# ESP32_sparrow_old_good.net
KiCad netlist of a schematic drawn in EAGLE
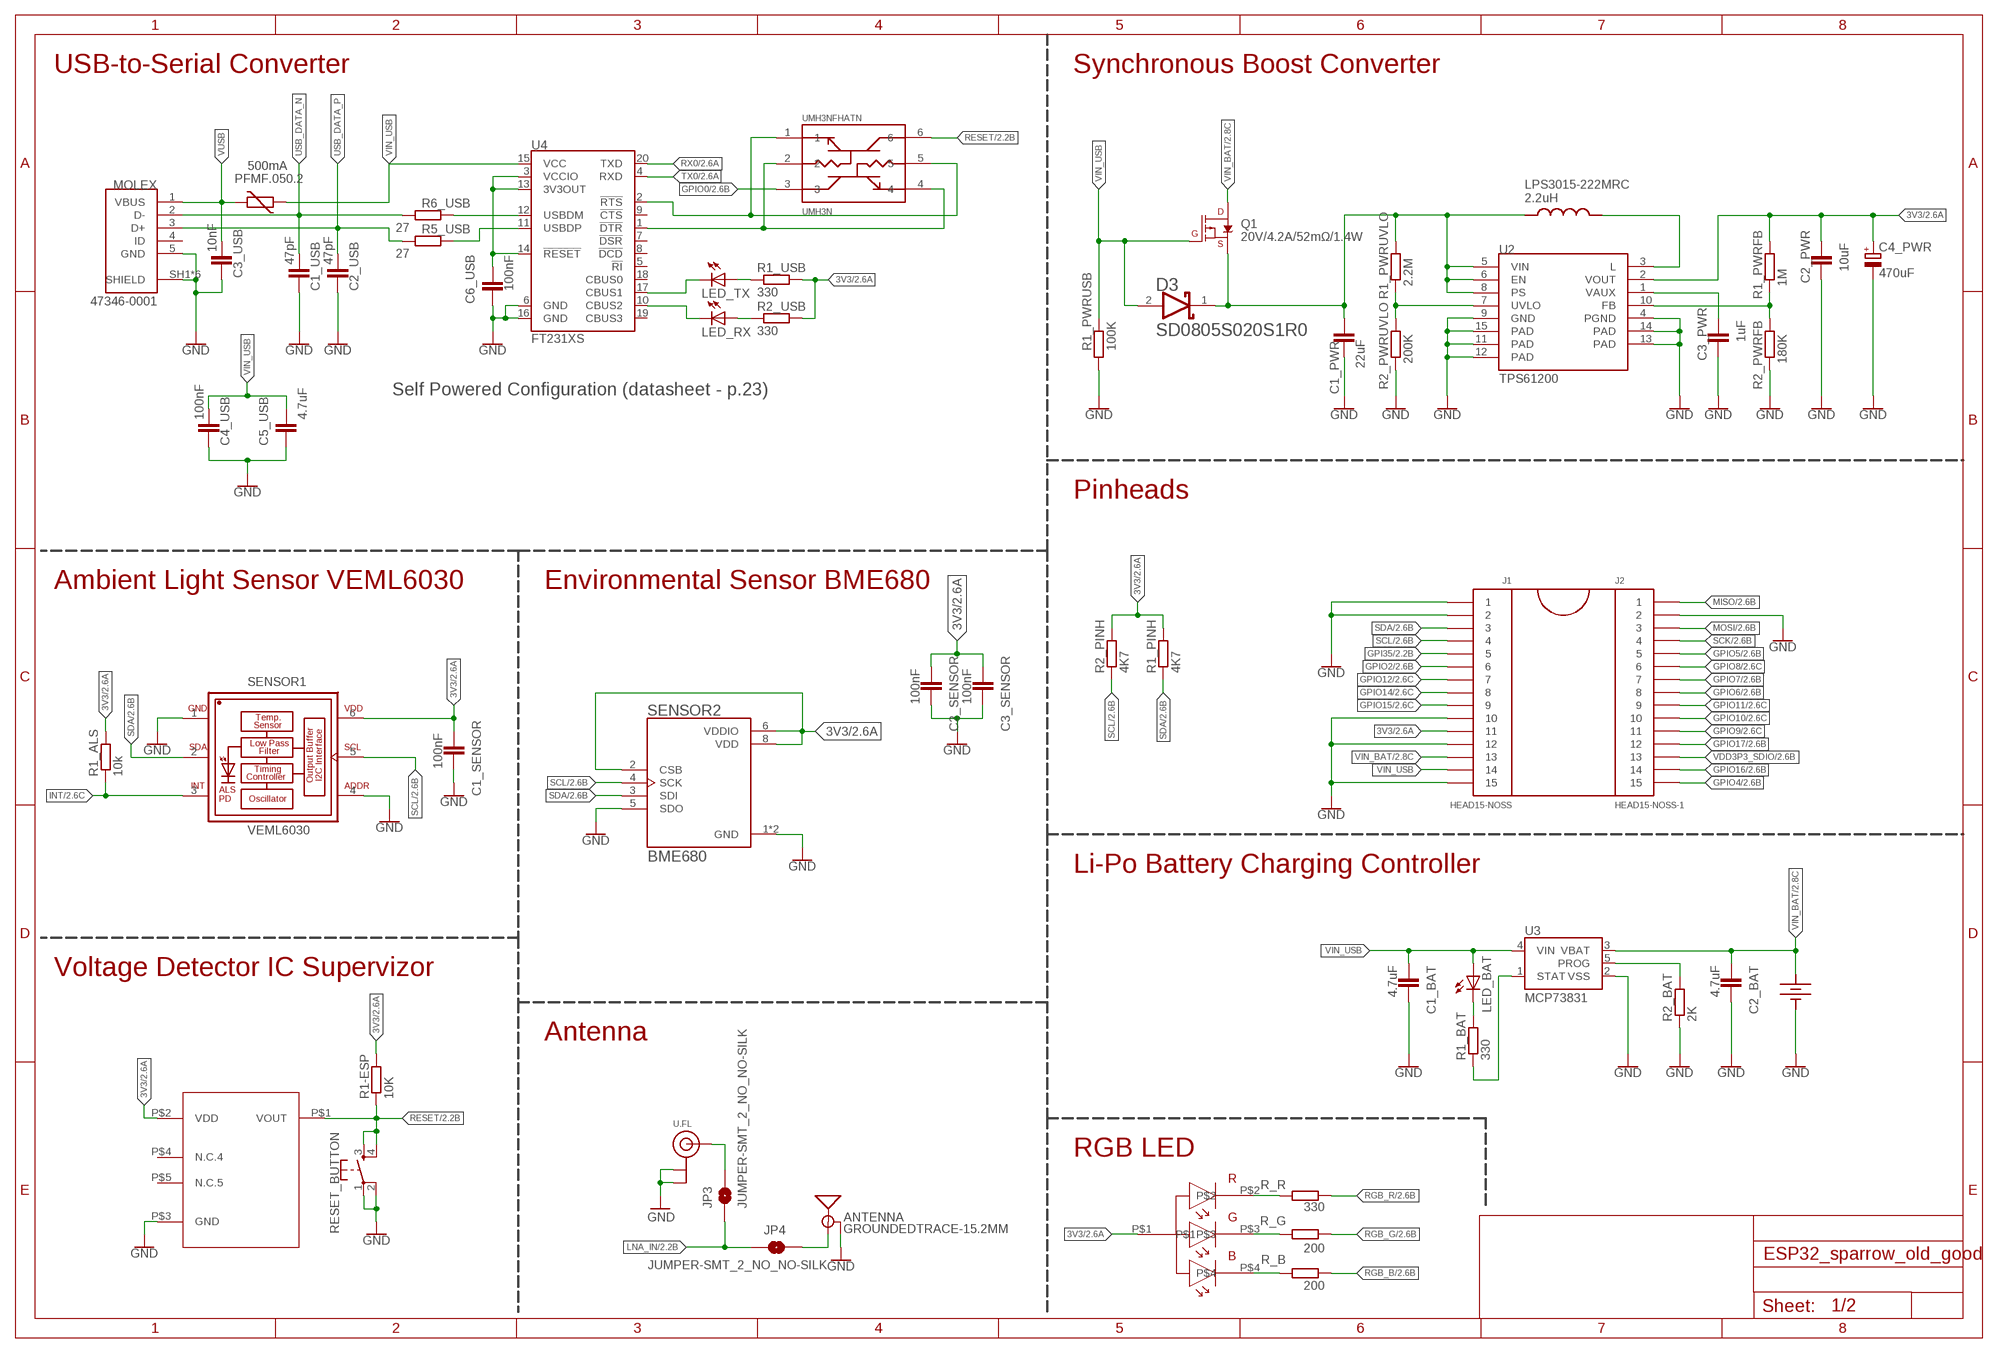
[diagram p0: schematic, sheet 1]
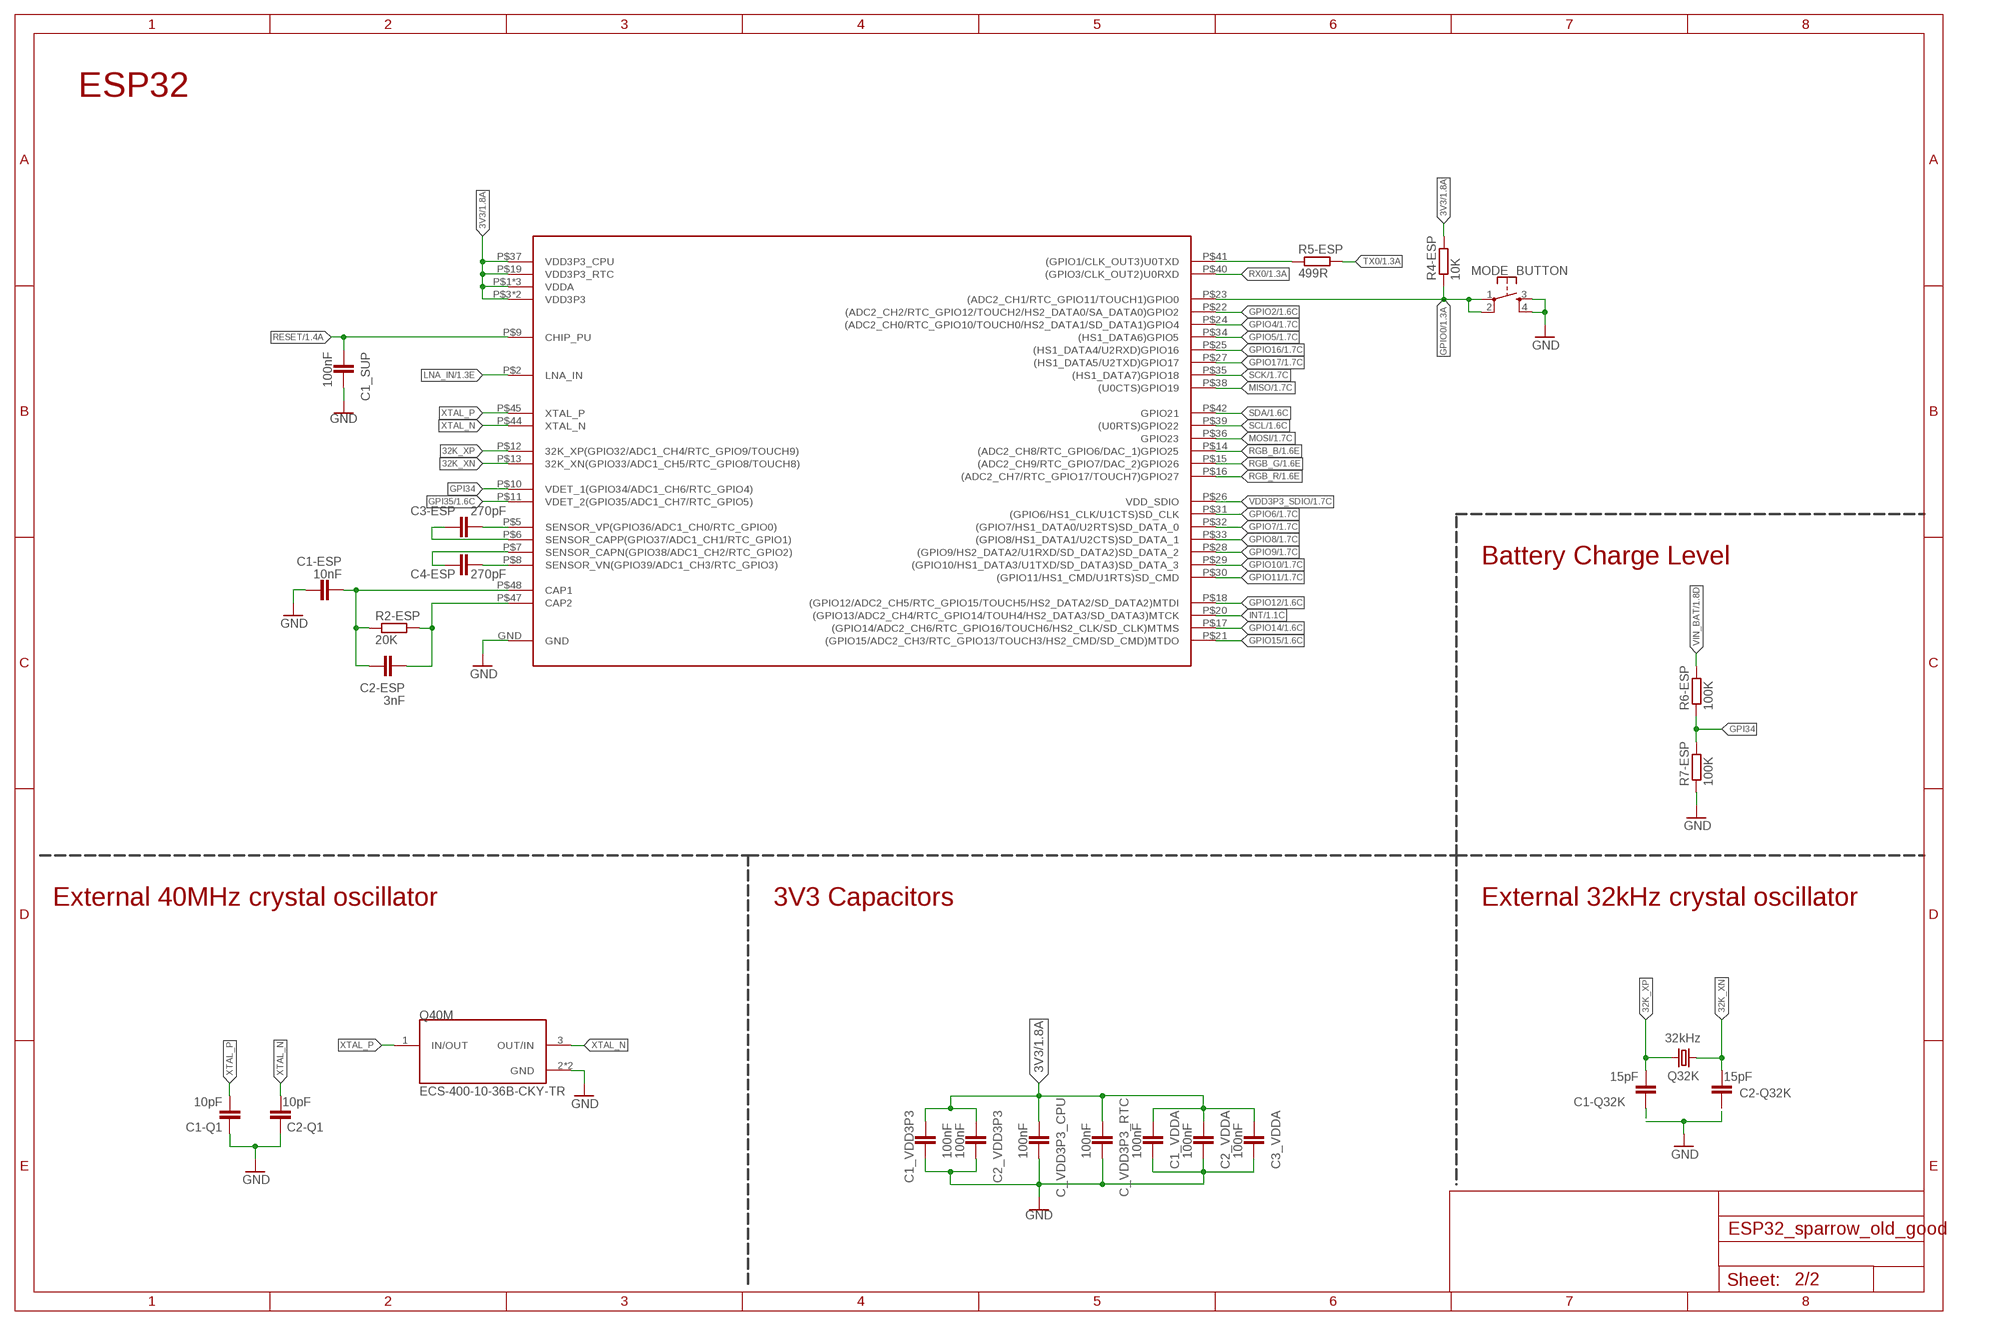
[diagram p1: schematic, sheet 2]

(export (version "E")
  (design (tool "Eeschema 10.0.6"))
  (components
    (comp (ref "C1-ESP")
      (value "10nF")
      (footprint "eagle-import:C0402")
      (libsource (lib "eagle-import") (part "CC0402"))
    )
    (comp (ref "C1-Q1")
      (value "10pF")
      (footprint "eagle-import:C0402")
      (libsource (lib "eagle-import") (part "CC0402"))
    )
    (comp (ref "C1-Q32K")
      (value "15pF")
      (footprint "eagle-import:C0402")
      (libsource (lib "eagle-import") (part "CC0402"))
    )
    (comp (ref "C1_SUP")
      (value "100nF")
      (footprint "eagle-import:C0402")
      (libsource (lib "eagle-import") (part "CC0402"))
    )
    (comp (ref "C1_VDD3P3")
      (value "100nF")
      (footprint "eagle-import:C0402")
      (libsource (lib "eagle-import") (part "CC0402"))
    )
    (comp (ref "C1_VDDA")
      (value "100nF")
      (footprint "eagle-import:C0402")
      (libsource (lib "eagle-import") (part "CC0402"))
    )
    (comp (ref "C2-ESP")
      (value "3nF")
      (footprint "eagle-import:C0402")
      (libsource (lib "eagle-import") (part "CC0402"))
    )
    (comp (ref "C2-Q1")
      (value "10pF")
      (footprint "eagle-import:C0402")
      (libsource (lib "eagle-import") (part "CC0402"))
    )
    (comp (ref "C2-Q32K")
      (value "15pF")
      (footprint "eagle-import:C0402")
      (libsource (lib "eagle-import") (part "CC0402"))
    )
    (comp (ref "C2_VDD3P3")
      (value "100nF")
      (footprint "eagle-import:C0402")
      (libsource (lib "eagle-import") (part "CC0402"))
    )
    (comp (ref "C2_VDDA")
      (value "100nF")
      (footprint "eagle-import:C0402")
      (libsource (lib "eagle-import") (part "CC0402"))
    )
    (comp (ref "C3-ESP")
      (value "270pF")
      (footprint "eagle-import:C0402")
      (libsource (lib "eagle-import") (part "CC0402"))
    )
    (comp (ref "C3_VDDA")
      (value "100nF")
      (footprint "eagle-import:C0402")
      (libsource (lib "eagle-import") (part "CC0402"))
    )
    (comp (ref "C4-ESP")
      (value "270pF")
      (footprint "eagle-import:C0402")
      (libsource (lib "eagle-import") (part "CC0402"))
    )
    (comp (ref "C_VDD3P3_CPU")
      (value "100nF")
      (footprint "eagle-import:C0402")
      (libsource (lib "eagle-import") (part "CC0402"))
    )
    (comp (ref "C_VDD3P3_RTC")
      (value "100nF")
      (footprint "eagle-import:C0402")
      (libsource (lib "eagle-import") (part "CC0402"))
    )
    (comp (ref "MODE_BUTTON")
      (value "MOMENTARY-SWITCH-SPST-2-SMD-4.6X2.8MM")
      (footprint "eagle-import:TACTILE_SWITCH_SMD_4.6X2.8MM")
      (libsource (lib "eagle-import") (part "MOMENTARY-SWITCH-SPST-2-SMD-4.6X2.8MM"))
    )
    (comp (ref "Q32K")
      (value "32kHz")
      (footprint "eagle-import:FC-12M")
      (libsource (lib "eagle-import") (part "FC-12M"))
    )
    (comp (ref "Q40M")
      (value "ECS-400-10-36B-CKY-TR")
      (footprint "eagle-import:XTAL_ECS-163.84-10-36-JGN-TR")
      (fields (field (name "MF") "ECS Inc."))
      (libsource (lib "eagle-import") (part "ECS-400-10-36B-CKY-TR"))
    )
    (comp (ref "R2-ESP")
      (value "20K")
      (footprint "eagle-import:R0402")
      (libsource (lib "eagle-import") (part "RR0402"))
    )
    (comp (ref "R4-ESP")
      (value "10K")
      (footprint "eagle-import:R0402")
      (libsource (lib "eagle-import") (part "RR0402"))
    )
    (comp (ref "R5-ESP")
      (value "499R")
      (footprint "eagle-import:R0402")
      (libsource (lib "eagle-import") (part "RR0402"))
    )
    (comp (ref "R6-ESP")
      (value "100K")
      (footprint "eagle-import:R0402")
      (libsource (lib "eagle-import") (part "RR0402"))
    )
    (comp (ref "R7-ESP")
      (value "100K")
      (footprint "eagle-import:R0402")
      (libsource (lib "eagle-import") (part "RR0402"))
    )
    (comp (ref "U$3")
      (value "ESP32-U4WDH")
      (footprint "eagle-import:ESP32-U4WDH")
      (libsource (lib "eagle-import") (part "ESP32-U4WDH"))
    )
    (comp (ref "ANTENNA")
      (value "GROUNDEDTRACE-15.2MM")
      (footprint "eagle-import:TRACE_ANTENNA_2.4GHZ_15.2MM")
      (libsource (lib "eagle-import") (part "ANTENNA-GROUNDEDTRACE-15.2MM"))
    )
    (comp (ref "C1_BAT")
      (value "4.7uF")
      (footprint "eagle-import:C0402")
      (libsource (lib "eagle-import") (part "CC0402"))
    )
    (comp (ref "C1_PWR")
      (value "22uF")
      (footprint "eagle-import:C0603")
      (libsource (lib "eagle-import") (part "C-EUC0603"))
    )
    (comp (ref "C1_SENSOR")
      (value "100nF")
      (footprint "eagle-import:C0402")
      (libsource (lib "eagle-import") (part "CC0402"))
    )
    (comp (ref "C1_USB")
      (value "47pF")
      (footprint "eagle-import:C0402")
      (libsource (lib "eagle-import") (part "CC0402"))
    )
    (comp (ref "C2_BAT")
      (value "4.7uF")
      (footprint "eagle-import:C0402")
      (libsource (lib "eagle-import") (part "CC0402"))
    )
    (comp (ref "C2_PWR")
      (value "10uF")
      (footprint "eagle-import:C0402")
      (libsource (lib "eagle-import") (part "CC0402"))
    )
    (comp (ref "C2_SENSOR")
      (value "100nF")
      (footprint "eagle-import:C0402")
      (libsource (lib "eagle-import") (part "CC0402"))
    )
    (comp (ref "C2_USB")
      (value "47pF")
      (footprint "eagle-import:C0402")
      (libsource (lib "eagle-import") (part "CC0402"))
    )
    (comp (ref "C3_PWR")
      (value "1uF")
      (footprint "eagle-import:C0402")
      (libsource (lib "eagle-import") (part "CC0402"))
    )
    (comp (ref "C3_SENSOR")
      (value "100nF")
      (footprint "eagle-import:C0402")
      (libsource (lib "eagle-import") (part "CC0402"))
    )
    (comp (ref "C3_USB")
      (value "10nF")
      (footprint "eagle-import:C0402")
      (libsource (lib "eagle-import") (part "CC0402"))
    )
    (comp (ref "C4_PWR")
      (value "470uF")
      (footprint "eagle-import:D_7343-31R")
      (libsource (lib "eagle-import") (part "CPOL-EUD/7343-31R"))
    )
    (comp (ref "C4_USB")
      (value "100nF")
      (footprint "eagle-import:C0402")
      (libsource (lib "eagle-import") (part "CC0402"))
    )
    (comp (ref "C5_USB")
      (value "4.7uF")
      (footprint "eagle-import:C0402")
      (libsource (lib "eagle-import") (part "CC0402"))
    )
    (comp (ref "C6_USB")
      (value "100nF")
      (footprint "eagle-import:C0402")
      (libsource (lib "eagle-import") (part "CC0402"))
    )
    (comp (ref "D3")
      (value "AVX_SD0805S020S1R0AVX_SD0805S020S1R0_0_0")
      (footprint "eagle-import:AVX_SD0805S020S1R0_0")
      (fields
        (field (name "DIGIKEY_PART_NUMBER") "478-7800-1-ND")
        (field (name "MF") "AVX")
        (field (name "MOUSER_PART_NUMBER") "581-SD0805S020S1R0")
      )
      (libsource (lib "eagle-import") (part "AVX_SD0805S020S1R0AVX_SD0805S020S1R0_0_0"))
    )
    (comp (ref "J1")
      (value "HEAD15-NOSS")
      (footprint "eagle-import:HEAD15-NOSS")
      (libsource (lib "eagle-import") (part "HEAD15-NOSS"))
    )
    (comp (ref "J2")
      (value "HEAD15-NOSS-1")
      (footprint "eagle-import:HEAD15-NOSS-1")
      (libsource (lib "eagle-import") (part "HEAD15-NOSS-1"))
    )
    (comp (ref "JP3")
      (value "JUMPER-SMT_2_NO_NO-SILK")
      (footprint "eagle-import:SMT-JUMPER_2_NO_NO-SILK")
      (libsource (lib "eagle-import") (part "JUMPER-SMT_2_NO_NO-SILK"))
    )
    (comp (ref "JP4")
      (value "JUMPER-SMT_2_NO_NO-SILK")
      (footprint "eagle-import:SMT-JUMPER_2_NO_NO-SILK")
      (libsource (lib "eagle-import") (part "JUMPER-SMT_2_NO_NO-SILK"))
    )
    (comp (ref "LED_BAT")
      (value "LEDCHIP-LED0603")
      (footprint "eagle-import:CHIP-LED0603")
      (libsource (lib "eagle-import") (part "LEDCHIP-LED0603"))
    )
    (comp (ref "LED_RX")
      (value "LEDCHIP-LED0603")
      (footprint "eagle-import:CHIP-LED0603")
      (libsource (lib "eagle-import") (part "LEDCHIP-LED0603"))
    )
    (comp (ref "LED_TX")
      (value "LEDCHIP-LED0603")
      (footprint "eagle-import:CHIP-LED0603")
      (libsource (lib "eagle-import") (part "LEDCHIP-LED0603"))
    )
    (comp (ref "MOLEX")
      (value "47346-0001")
      (footprint "eagle-import:MOLEX_47346-0001")
      (fields (field (name "MF") "Molex"))
      (libsource (lib "eagle-import") (part "47346-0001"))
    )
    (comp (ref "PFMF.050.2")
      (value "500mA")
      (footprint "eagle-import:CT_CN1812")
      (libsource (lib "eagle-import") (part "VARISTORCN1812"))
    )
    (comp (ref "Q1")
      (value "20V/4.2A/52mΩ/1.4W")
      (footprint "eagle-import:SOT23-3")
      (libsource (lib "eagle-import") (part "MOSFET_PCH-DMG2305UX-7"))
    )
    (comp (ref "R1-ESP")
      (value "10K")
      (footprint "eagle-import:R0402")
      (libsource (lib "eagle-import") (part "RR0402"))
    )
    (comp (ref "R1_ALS")
      (value "10k")
      (footprint "eagle-import:R0402")
      (libsource (lib "eagle-import") (part "RR0402"))
    )
    (comp (ref "R1_BAT")
      (value "330")
      (footprint "eagle-import:R0402")
      (libsource (lib "eagle-import") (part "RR0402"))
    )
    (comp (ref "R1_PINH")
      (value "4K7")
      (footprint "eagle-import:R0402")
      (libsource (lib "eagle-import") (part "RR0402"))
    )
    (comp (ref "R1_PWRFB")
      (value "1M")
      (footprint "eagle-import:R0402")
      (libsource (lib "eagle-import") (part "RR0402"))
    )
    (comp (ref "R1_PWRUSB")
      (value "100K")
      (footprint "eagle-import:R0402")
      (libsource (lib "eagle-import") (part "RR0402"))
    )
    (comp (ref "R1_PWRUVLO")
      (value "2.2M")
      (footprint "eagle-import:R0402")
      (libsource (lib "eagle-import") (part "RR0402"))
    )
    (comp (ref "R1_USB")
      (value "330")
      (footprint "eagle-import:R0402")
      (libsource (lib "eagle-import") (part "RR0402"))
    )
    (comp (ref "R2_BAT")
      (value "2K")
      (footprint "eagle-import:R0402")
      (libsource (lib "eagle-import") (part "RR0402"))
    )
    (comp (ref "R2_PINH")
      (value "4K7")
      (footprint "eagle-import:R0402")
      (libsource (lib "eagle-import") (part "RR0402"))
    )
    (comp (ref "R2_PWRFB")
      (value "180K")
      (footprint "eagle-import:R0402")
      (libsource (lib "eagle-import") (part "RR0402"))
    )
    (comp (ref "R2_PWRUVLO")
      (value "200K")
      (footprint "eagle-import:R0402")
      (libsource (lib "eagle-import") (part "RR0402"))
    )
    (comp (ref "R2_USB")
      (value "330")
      (footprint "eagle-import:R0402")
      (libsource (lib "eagle-import") (part "RR0402"))
    )
    (comp (ref "R5_USB")
      (value "27")
      (footprint "eagle-import:R0402")
      (libsource (lib "eagle-import") (part "RR0402"))
    )
    (comp (ref "R6_USB")
      (value "27")
      (footprint "eagle-import:R0402")
      (libsource (lib "eagle-import") (part "RR0402"))
    )
    (comp (ref "RESET_BUTTON")
      (value "MOMENTARY-SWITCH-SPST-2-SMD-4.6X2.8MM")
      (footprint "eagle-import:TACTILE_SWITCH_SMD_4.6X2.8MM")
      (libsource (lib "eagle-import") (part "MOMENTARY-SWITCH-SPST-2-SMD-4.6X2.8MM"))
    )
    (comp (ref "R_B")
      (value "200")
      (footprint "eagle-import:R0402")
      (libsource (lib "eagle-import") (part "eagle-ltspice_217_RR0402"))
    )
    (comp (ref "R_G")
      (value "200")
      (footprint "eagle-import:R0402")
      (libsource (lib "eagle-import") (part "eagle-ltspice_217_RR0402"))
    )
    (comp (ref "R_R")
      (value "330")
      (footprint "eagle-import:R0402")
      (libsource (lib "eagle-import") (part "eagle-ltspice_217_RR0402"))
    )
    (comp (ref "SENSOR1")
      (value "VEML6030")
      (footprint "eagle-import:VISHAY_VEML6030_2X2X0.87")
      (fields (field (name "MF") "Vishay"))
      (libsource (lib "eagle-import") (part "VEML6030"))
    )
    (comp (ref "SENSOR2")
      (value "BME680")
      (footprint "eagle-import:PSON80P300X300X100-8N")
      (fields (field (name "MF") "Bosch Sensortec"))
      (libsource (lib "eagle-import") (part "BME680"))
    )
    (comp (ref "U$1")
      (value "150202M153130-RGB")
      (footprint "eagle-import:150202M153130")
      (libsource (lib "eagle-import") (part "150202M153130-RGB"))
    )
    (comp (ref "U$2")
      (value "BD48E27G-TR")
      (footprint "eagle-import:SSOP5")
      (libsource (lib "eagle-import") (part "BD48E27G-TR"))
    )
    (comp (ref "U$4")
      (value "12BHC186CLP-GR")
      (footprint "eagle-import:12BHC186CLP-GR")
      (libsource (lib "eagle-import") (part "12BHC186CLP-GR"))
    )
    (comp (ref "U$5")
      (value "LPS3015")
      (footprint "eagle-import:LPS3015-222MRC")
      (libsource (lib "eagle-import") (part "LPS3015"))
    )
    (comp (ref "U.FL")
      (value "ANTENNA_U.FL")
      (footprint "eagle-import:U.FL")
      (libsource (lib "eagle-import") (part "ANTENNA_U.FL"))
    )
    (comp (ref "U2")
      (value "TPS61200")
      (footprint "eagle-import:QFN-10_PAD")
      (libsource (lib "eagle-import") (part "TPS61200"))
    )
    (comp (ref "U3")
      (value "MCP73831")
      (footprint "eagle-import:SOT23-5")
      (libsource (lib "eagle-import") (part "MCP73831"))
    )
    (comp (ref "U4")
      (value "FT231XS")
      (footprint "eagle-import:SSOP20_L")
      (libsource (lib "eagle-import") (part "FT231XS"))
    )
    (comp (ref "UMH3NFHATN")
      (value "UMH3NFHATN")
      (footprint "eagle-import:SOP65P210X100-6N")
      (fields (field (name "MF") "Rohm") (field (name "MP") "UMH3N"))
      (libsource (lib "eagle-import") (part "UMH3N"))
    )
  )
  (nets
    (net (code "1") (name "3V3") (class "Default")
      (node (ref "C1_SENSOR") (pin "2") (pinfunction "2_2") (pintype "passive"))
      (node (ref "C1_VDD3P3") (pin "2") (pinfunction "2_2") (pintype "passive"))
      (node (ref "C1_VDDA") (pin "2") (pinfunction "2_2") (pintype "passive"))
      (node (ref "C2_PWR") (pin "2") (pinfunction "2_2") (pintype "passive"))
      (node (ref "C2_SENSOR") (pin "2") (pinfunction "2_2") (pintype "passive"))
      (node (ref "C2_VDD3P3") (pin "2") (pinfunction "2_2") (pintype "passive"))
      (node (ref "C2_VDDA") (pin "2") (pinfunction "2_2") (pintype "passive"))
      (node (ref "C3_SENSOR") (pin "2") (pinfunction "2_2") (pintype "passive"))
      (node (ref "C3_VDDA") (pin "2") (pinfunction "2_2") (pintype "passive"))
      (node (ref "C4_PWR") (pin "+") (pinfunction "+_+") (pintype "passive"))
      (node (ref "C_VDD3P3_CPU") (pin "2") (pinfunction "2_2") (pintype "passive"))
      (node (ref "C_VDD3P3_RTC") (pin "2") (pinfunction "2_2") (pintype "passive"))
      (node (ref "J1") (pin "11") (pinfunction "11_11") (pintype "passive"))
      (node (ref "R1-ESP") (pin "2") (pinfunction "2_2") (pintype "passive"))
      (node (ref "R1_ALS") (pin "2") (pinfunction "2_2") (pintype "passive"))
      (node (ref "R1_PINH") (pin "2") (pinfunction "2_2") (pintype "passive"))
      (node (ref "R1_PWRFB") (pin "2") (pinfunction "2_2") (pintype "passive"))
      (node (ref "R1_USB") (pin "2") (pinfunction "2_2") (pintype "passive"))
      (node (ref "R2_PINH") (pin "2") (pinfunction "2_2") (pintype "passive"))
      (node (ref "R2_USB") (pin "2") (pinfunction "2_2") (pintype "passive"))
      (node (ref "R4-ESP") (pin "2") (pinfunction "2_2") (pintype "passive"))
      (node (ref "SENSOR1") (pin "6") (pinfunction "VDD_6") (pintype "power_in"))
      (node (ref "SENSOR2") (pin "2") (pinfunction "CSB_2") (pintype "input"))
      (node (ref "SENSOR2") (pin "6") (pinfunction "VDDIO_6") (pintype "power_in"))
      (node (ref "SENSOR2") (pin "8") (pinfunction "VDD_8") (pintype "power_in"))
      (node (ref "U$1") (pin "P$1") (pinfunction "P$1_P$1") (pintype "bidirectional"))
      (node (ref "U$2") (pin "P$2") (pinfunction "VDD_P$2") (pintype "bidirectional"))
      (node (ref "U$3") (pin "P$1") (pinfunction "VDDA_P$1") (pintype "bidirectional"))
      (node (ref "U$3") (pin "P$19") (pinfunction "VDD3P3_RTC_P$19") (pintype "bidirectional"))
      (node (ref "U$3") (pin "P$3") (pinfunction "VDD3P3_P$3") (pintype "bidirectional"))
      (node (ref "U$3") (pin "P$37") (pinfunction "VDD3P3_CPU_P$37") (pintype "bidirectional"))
      (node (ref "U$3") (pin "P$4") (pinfunction "VDD3P3_P$4") (pintype "bidirectional"))
      (node (ref "U$3") (pin "P$43") (pinfunction "VDDA_P$43") (pintype "bidirectional"))
      (node (ref "U$3") (pin "P$46") (pinfunction "VDDA_P$46") (pintype "bidirectional"))
      (node (ref "U2") (pin "2") (pinfunction "VOUT_2") (pintype "passive"))
    )
    (net (code "2") (name "32K_XN") (class "Default")
      (node (ref "C2-Q32K") (pin "2") (pinfunction "2_2") (pintype "passive"))
      (node (ref "Q32K") (pin "1") (pinfunction "1_1") (pintype "passive"))
      (node (ref "U$3") (pin "P$13") (pinfunction "32K_XN(GPIO33/ADC1_CH5/RTC_GPIO8/TOUCH8)_P$13") (pintype "bidirectional"))
    )
    (net (code "3") (name "32K_XP") (class "Default")
      (node (ref "C1-Q32K") (pin "2") (pinfunction "2_2") (pintype "passive"))
      (node (ref "Q32K") (pin "2") (pinfunction "2_2") (pintype "passive"))
      (node (ref "U$3") (pin "P$12") (pinfunction "32K_XP(GPIO32/ADC1_CH4/RTC_GPIO9/TOUCH9)_P$12") (pintype "bidirectional"))
    )
    (net (code "4") (name "GND") (class "Default")
      (node (ref "ANTENNA") (pin "GND") (pinfunction "GND_GND") (pintype "bidirectional"))
      (node (ref "C1-ESP") (pin "1") (pinfunction "1_1") (pintype "passive"))
      (node (ref "C1-Q1") (pin "1") (pinfunction "1_1") (pintype "passive"))
      (node (ref "C1-Q32K") (pin "1") (pinfunction "1_1") (pintype "passive"))
      (node (ref "C1_BAT") (pin "1") (pinfunction "1_1") (pintype "passive"))
      (node (ref "C1_PWR") (pin "2") (pinfunction "2_2") (pintype "passive"))
      (node (ref "C1_SENSOR") (pin "1") (pinfunction "1_1") (pintype "passive"))
      (node (ref "C1_SUP") (pin "1") (pinfunction "1_1") (pintype "passive"))
      (node (ref "C1_USB") (pin "2") (pinfunction "2_2") (pintype "passive"))
      (node (ref "C1_VDD3P3") (pin "1") (pinfunction "1_1") (pintype "passive"))
      (node (ref "C1_VDDA") (pin "1") (pinfunction "1_1") (pintype "passive"))
      (node (ref "C2-Q1") (pin "1") (pinfunction "1_1") (pintype "passive"))
      (node (ref "C2-Q32K") (pin "1") (pinfunction "1_1") (pintype "passive"))
      (node (ref "C2_BAT") (pin "1") (pinfunction "1_1") (pintype "passive"))
      (node (ref "C2_PWR") (pin "1") (pinfunction "1_1") (pintype "passive"))
      (node (ref "C2_SENSOR") (pin "1") (pinfunction "1_1") (pintype "passive"))
      (node (ref "C2_USB") (pin "2") (pinfunction "2_2") (pintype "passive"))
      (node (ref "C2_VDD3P3") (pin "1") (pinfunction "1_1") (pintype "passive"))
      (node (ref "C2_VDDA") (pin "1") (pinfunction "1_1") (pintype "passive"))
      (node (ref "C3_PWR") (pin "1") (pinfunction "1_1") (pintype "passive"))
      (node (ref "C3_SENSOR") (pin "1") (pinfunction "1_1") (pintype "passive"))
      (node (ref "C3_USB") (pin "2") (pinfunction "2_2") (pintype "passive"))
      (node (ref "C3_VDDA") (pin "1") (pinfunction "1_1") (pintype "passive"))
      (node (ref "C4_PWR") (pin "-") (pinfunction "-_-") (pintype "passive"))
      (node (ref "C4_USB") (pin "2") (pinfunction "2_2") (pintype "passive"))
      (node (ref "C5_USB") (pin "2") (pinfunction "2_2") (pintype "passive"))
      (node (ref "C6_USB") (pin "2") (pinfunction "2_2") (pintype "passive"))
      (node (ref "C_VDD3P3_CPU") (pin "1") (pinfunction "1_1") (pintype "passive"))
      (node (ref "C_VDD3P3_RTC") (pin "1") (pinfunction "1_1") (pintype "passive"))
      (node (ref "J1") (pin "1") (pinfunction "1_1") (pintype "passive"))
      (node (ref "J1") (pin "10") (pinfunction "10_10") (pintype "passive"))
      (node (ref "J1") (pin "12") (pinfunction "12_12") (pintype "passive"))
      (node (ref "J1") (pin "15") (pinfunction "15_15") (pintype "passive"))
      (node (ref "J1") (pin "2") (pinfunction "2_2") (pintype "passive"))
      (node (ref "J2") (pin "2") (pinfunction "2_2") (pintype "passive"))
      (node (ref "MODE_BUTTON") (pin "3") (pinfunction "3_3") (pintype "passive"))
      (node (ref "MODE_BUTTON") (pin "4") (pinfunction "4_4") (pintype "passive"))
      (node (ref "MOLEX") (pin "5") (pinfunction "GND_5") (pintype "power_in"))
      (node (ref "MOLEX") (pin "SH1") (pinfunction "SHIELD_SH1") (pintype "passive"))
      (node (ref "MOLEX") (pin "SH2") (pinfunction "SHIELD_SH2") (pintype "passive"))
      (node (ref "MOLEX") (pin "SH3") (pinfunction "SHIELD_SH3") (pintype "passive"))
      (node (ref "MOLEX") (pin "SH4") (pinfunction "SHIELD_SH4") (pintype "passive"))
      (node (ref "MOLEX") (pin "SH5") (pinfunction "SHIELD_SH5") (pintype "passive"))
      (node (ref "MOLEX") (pin "SH6") (pinfunction "SHIELD_SH6") (pintype "passive"))
      (node (ref "Q40M") (pin "2") (pinfunction "GND_2") (pintype "power_in"))
      (node (ref "Q40M") (pin "4") (pinfunction "GND_4") (pintype "power_in"))
      (node (ref "R1_PWRUSB") (pin "1") (pinfunction "1_1") (pintype "passive"))
      (node (ref "R2_BAT") (pin "1") (pinfunction "1_1") (pintype "passive"))
      (node (ref "R2_PWRFB") (pin "1") (pinfunction "1_1") (pintype "passive"))
      (node (ref "R2_PWRUVLO") (pin "1") (pinfunction "1_1") (pintype "passive"))
      (node (ref "R7-ESP") (pin "1") (pinfunction "1_1") (pintype "passive"))
      (node (ref "RESET_BUTTON") (pin "1") (pinfunction "1_1") (pintype "passive"))
      (node (ref "RESET_BUTTON") (pin "2") (pinfunction "2_2") (pintype "passive"))
      (node (ref "SENSOR1") (pin "1") (pinfunction "GND_1") (pintype "power_in"))
      (node (ref "SENSOR1") (pin "4") (pinfunction "ADDR_4") (pintype "bidirectional"))
      (node (ref "SENSOR2") (pin "1") (pinfunction "GND_1") (pintype "power_in"))
      (node (ref "SENSOR2") (pin "5") (pinfunction "SDO_5") (pintype "bidirectional"))
      (node (ref "SENSOR2") (pin "7") (pinfunction "GND_7") (pintype "power_in"))
      (node (ref "U$2") (pin "P$3") (pinfunction "GND_P$3") (pintype "bidirectional"))
      (node (ref "U$3") (pin "GND") (pinfunction "GND_GND") (pintype "bidirectional"))
      (node (ref "U$4") (pin "P$1") (pinfunction "G_P$1") (pintype "bidirectional"))
      (node (ref "U$4") (pin "P$3") (pinfunction "G_P$3") (pintype "bidirectional"))
      (node (ref "U$4") (pin "P$4") (pinfunction "G_P$4") (pintype "bidirectional"))
      (node (ref "U.FL") (pin "1") (pinfunction "GND_1") (pintype "passive"))
      (node (ref "U.FL") (pin "2") (pinfunction "GND_2") (pintype "passive"))
      (node (ref "U2") (pin "11") (pinfunction "PAD_11") (pintype "power_in"))
      (node (ref "U2") (pin "12") (pinfunction "PAD_12") (pintype "power_in"))
      (node (ref "U2") (pin "13") (pinfunction "PAD_13") (pintype "power_in"))
      (node (ref "U2") (pin "14") (pinfunction "PAD_14") (pintype "power_in"))
      (node (ref "U2") (pin "15") (pinfunction "PAD_15") (pintype "power_in"))
      (node (ref "U2") (pin "4") (pinfunction "PGND_4") (pintype "power_in"))
      (node (ref "U2") (pin "9") (pinfunction "GND_9") (pintype "power_in"))
      (node (ref "U3") (pin "2") (pinfunction "VSS_2") (pintype "power_in"))
      (node (ref "U4") (pin "16") (pinfunction "GND_16") (pintype "bidirectional"))
      (node (ref "U4") (pin "6") (pinfunction "GND_6") (pintype "bidirectional"))
    )
    (net (code "5") (name "GPI34") (class "Default")
      (node (ref "R6-ESP") (pin "1") (pinfunction "1_1") (pintype "passive"))
      (node (ref "R7-ESP") (pin "2") (pinfunction "2_2") (pintype "passive"))
      (node (ref "U$3") (pin "P$10") (pinfunction "VDET_1(GPIO34/ADC1_CH6/RTC_GPIO4)_P$10") (pintype "bidirectional"))
    )
    (net (code "6") (name "GPI35") (class "Default")
      (node (ref "J1") (pin "5") (pinfunction "5_5") (pintype "passive"))
      (node (ref "U$3") (pin "P$11") (pinfunction "VDET_2(GPIO35/ADC1_CH7/RTC_GPIO5)_P$11") (pintype "bidirectional"))
    )
    (net (code "7") (name "GPIO0") (class "Default")
      (node (ref "MODE_BUTTON") (pin "1") (pinfunction "1_1") (pintype "passive"))
      (node (ref "MODE_BUTTON") (pin "2") (pinfunction "2_2") (pintype "passive"))
      (node (ref "R4-ESP") (pin "1") (pinfunction "1_1") (pintype "passive"))
      (node (ref "U$3") (pin "P$23") (pinfunction "(ADC2_CH1/RTC_GPIO11/TOUCH1)GPIO0_P$23") (pintype "bidirectional"))
      (node (ref "UMH3NFHATN") (pin "3") (pinfunction "3_3") (pintype "bidirectional"))
    )
    (net (code "8") (name "GPIO2") (class "Default")
      (node (ref "J1") (pin "6") (pinfunction "6_6") (pintype "passive"))
      (node (ref "U$3") (pin "P$22") (pinfunction "(ADC2_CH2/RTC_GPIO12/TOUCH2/HS2_DATA0/SA_DATA0)GPIO2_P$22") (pintype "bidirectional"))
    )
    (net (code "9") (name "GPIO4") (class "Default")
      (node (ref "J2") (pin "15") (pinfunction "15_15") (pintype "passive"))
      (node (ref "U$3") (pin "P$24") (pinfunction "(ADC2_CH0/RTC_GPIO10/TOUCH0/HS2_DATA1/SD_DATA1)GPIO4_P$24") (pintype "bidirectional"))
    )
    (net (code "10") (name "GPIO5") (class "Default")
      (node (ref "J2") (pin "5") (pinfunction "5_5") (pintype "passive"))
      (node (ref "U$3") (pin "P$34") (pinfunction "(HS1_DATA6)GPIO5_P$34") (pintype "bidirectional"))
    )
    (net (code "11") (name "GPIO6") (class "Default")
      (node (ref "J2") (pin "8") (pinfunction "8_8") (pintype "passive"))
      (node (ref "U$3") (pin "P$31") (pinfunction "(GPIO6/HS1_CLK/U1CTS)SD_CLK_P$31") (pintype "bidirectional"))
    )
    (net (code "12") (name "GPIO7") (class "Default")
      (node (ref "J2") (pin "7") (pinfunction "7_7") (pintype "passive"))
      (node (ref "U$3") (pin "P$32") (pinfunction "(GPIO7/HS1_DATA0/U2RTS)SD_DATA_0_P$32") (pintype "bidirectional"))
    )
    (net (code "13") (name "GPIO8") (class "Default")
      (node (ref "J2") (pin "6") (pinfunction "6_6") (pintype "passive"))
      (node (ref "U$3") (pin "P$33") (pinfunction "(GPIO8/HS1_DATA1/U2CTS)SD_DATA_1_P$33") (pintype "bidirectional"))
    )
    (net (code "14") (name "GPIO9") (class "Default")
      (node (ref "J2") (pin "11") (pinfunction "11_11") (pintype "passive"))
      (node (ref "U$3") (pin "P$28") (pinfunction "(GPIO9/HS2_DATA2/U1RXD/SD_DATA2)SD_DATA_2_P$28") (pintype "bidirectional"))
    )
    (net (code "15") (name "GPIO10") (class "Default")
      (node (ref "J2") (pin "10") (pinfunction "10_10") (pintype "passive"))
      (node (ref "U$3") (pin "P$29") (pinfunction "(GPIO10/HS1_DATA3/U1TXD/SD_DATA3)SD_DATA_3_P$29") (pintype "bidirectional"))
    )
    (net (code "16") (name "GPIO11") (class "Default")
      (node (ref "J2") (pin "9") (pinfunction "9_9") (pintype "passive"))
      (node (ref "U$3") (pin "P$30") (pinfunction "(GPIO11/HS1_CMD/U1RTS)SD_CMD_P$30") (pintype "bidirectional"))
    )
    (net (code "17") (name "GPIO12") (class "Default")
      (node (ref "J1") (pin "7") (pinfunction "7_7") (pintype "passive"))
      (node (ref "U$3") (pin "P$18") (pinfunction "(GPIO12/ADC2_CH5/RTC_GPIO15/TOUCH5/HS2_DATA2/SD_DATA2)MTDI_P$18") (pintype "bidirectional"))
    )
    (net (code "18") (name "GPIO14") (class "Default")
      (node (ref "J1") (pin "8") (pinfunction "8_8") (pintype "passive"))
      (node (ref "U$3") (pin "P$17") (pinfunction "(GPIO14/ADC2_CH6/RTC_GPIO16/TOUCH6/HS2_CLK/SD_CLK)MTMS_P$17") (pintype "bidirectional"))
    )
    (net (code "19") (name "GPIO15") (class "Default")
      (node (ref "J1") (pin "9") (pinfunction "9_9") (pintype "passive"))
      (node (ref "U$3") (pin "P$21") (pinfunction "(GPIO15/ADC2_CH3/RTC_GPIO13/TOUCH3/HS2_CMD/SD_CMD)MTDO_P$21") (pintype "bidirectional"))
    )
    (net (code "20") (name "GPIO16") (class "Default")
      (node (ref "J2") (pin "14") (pinfunction "14_14") (pintype "passive"))
      (node (ref "U$3") (pin "P$25") (pinfunction "(HS1_DATA4/U2RXD)GPIO16_P$25") (pintype "bidirectional"))
    )
    (net (code "21") (name "GPIO17") (class "Default")
      (node (ref "J2") (pin "12") (pinfunction "12_12") (pintype "passive"))
      (node (ref "U$3") (pin "P$27") (pinfunction "(HS1_DATA5/U2TXD)GPIO17_P$27") (pintype "bidirectional"))
    )
    (net (code "22") (name "INT") (class "Default")
      (node (ref "R1_ALS") (pin "1") (pinfunction "1_1") (pintype "passive"))
      (node (ref "SENSOR1") (pin "3") (pinfunction "INT_3") (pintype "output"))
      (node (ref "U$3") (pin "P$20") (pinfunction "(GPIO13/ADC2_CH4/RTC_GPIO14/TOUH4/HS2_DATA3/SD_DATA3)MTCK_P$20") (pintype "bidirectional"))
    )
    (net (code "23") (name "LNA_IN") (class "Default")
      (node (ref "JP3") (pin "1") (pinfunction "1_1") (pintype "passive"))
      (node (ref "JP4") (pin "1") (pinfunction "1_1") (pintype "passive"))
      (node (ref "U$3") (pin "P$2") (pinfunction "LNA_IN_P$2") (pintype "bidirectional"))
    )
    (net (code "24") (name "MISO") (class "Default")
      (node (ref "J2") (pin "1") (pinfunction "1_1") (pintype "passive"))
      (node (ref "U$3") (pin "P$38") (pinfunction "(U0CTS)GPIO19_P$38") (pintype "bidirectional"))
    )
    (net (code "25") (name "MOSI") (class "Default")
      (node (ref "J2") (pin "3") (pinfunction "3_3") (pintype "passive"))
      (node (ref "U$3") (pin "P$36") (pinfunction "GPIO23_P$36") (pintype "bidirectional"))
    )
    (net (code "26") (name "Net-(ANTENNA-SIGNAL)") (class "Default")
      (node (ref "ANTENNA") (pin "ANT") (pinfunction "SIGNAL_ANT") (pintype "bidirectional"))
      (node (ref "JP4") (pin "2") (pinfunction "2_2") (pintype "passive"))
    )
    (net (code "27") (name "Net-(D3-CATHODE)") (class "Default")
      (node (ref "C1_PWR") (pin "1") (pinfunction "1_1") (pintype "passive"))
      (node (ref "D3") (pin "1") (pinfunction "CATHODE_1") (pintype "bidirectional"))
      (node (ref "Q1") (pin "2") (pinfunction "S_2") (pintype "bidirectional"))
      (node (ref "R1_PWRUVLO") (pin "2") (pinfunction "2_2") (pintype "passive"))
      (node (ref "U$5") (pin "P$1") (pinfunction "P$1_P$1") (pintype "bidirectional"))
      (node (ref "U2") (pin "5") (pinfunction "VIN_5") (pintype "power_in"))
      (node (ref "U2") (pin "6") (pinfunction "EN_6") (pintype "input"))
      (node (ref "U2") (pin "8") (pinfunction "PS_8") (pintype "input"))
    )
    (net (code "28") (name "Net-(LED_BAT-PadC)") (class "Default")
      (node (ref "LED_BAT") (pin "C") (pinfunction "C_C") (pintype "passive"))
      (node (ref "R1_BAT") (pin "2") (pinfunction "2_2") (pintype "passive"))
    )
    (net (code "29") (name "Net-(LED_RX-PadA)") (class "Default")
      (node (ref "LED_RX") (pin "A") (pinfunction "A_A") (pintype "passive"))
      (node (ref "R2_USB") (pin "1") (pinfunction "1_1") (pintype "passive"))
    )
    (net (code "30") (name "Net-(LED_TX-PadA)") (class "Default")
      (node (ref "LED_TX") (pin "A") (pinfunction "A_A") (pintype "passive"))
      (node (ref "R1_USB") (pin "1") (pinfunction "1_1") (pintype "passive"))
    )
    (net (code "31") (name "Net-(R_B-Pad2)") (class "Default")
      (node (ref "R_B") (pin "2") (pinfunction "2_2") (pintype "passive"))
      (node (ref "U$1") (pin "P$4") (pinfunction "P$4_P$4") (pintype "bidirectional"))
    )
    (net (code "32") (name "Net-(R_G-Pad2)") (class "Default")
      (node (ref "R_G") (pin "2") (pinfunction "2_2") (pintype "passive"))
      (node (ref "U$1") (pin "P$3") (pinfunction "P$3_P$3") (pintype "bidirectional"))
    )
    (net (code "33") (name "Net-(R_R-Pad2)") (class "Default")
      (node (ref "R_R") (pin "2") (pinfunction "2_2") (pintype "passive"))
      (node (ref "U$1") (pin "P$2") (pinfunction "P$2_P$2") (pintype "bidirectional"))
    )
    (net (code "34") (name "Net-(U$3-(GPIO1{slash}CLK_OUT3)U0TXD)") (class "Default")
      (node (ref "R5-ESP") (pin "1") (pinfunction "1_1") (pintype "passive"))
      (node (ref "U$3") (pin "P$41") (pinfunction "(GPIO1/CLK_OUT3)U0TXD_P$41") (pintype "bidirectional"))
    )
    (net (code "35") (name "Net-(U$3-CAP1)") (class "Default")
      (node (ref "C1-ESP") (pin "2") (pinfunction "2_2") (pintype "passive"))
      (node (ref "C2-ESP") (pin "1") (pinfunction "1_1") (pintype "passive"))
      (node (ref "R2-ESP") (pin "1") (pinfunction "1_1") (pintype "passive"))
      (node (ref "U$3") (pin "P$48") (pinfunction "CAP1_P$48") (pintype "bidirectional"))
    )
    (net (code "36") (name "Net-(U$3-CAP2)") (class "Default")
      (node (ref "C2-ESP") (pin "2") (pinfunction "2_2") (pintype "passive"))
      (node (ref "R2-ESP") (pin "2") (pinfunction "2_2") (pintype "passive"))
      (node (ref "U$3") (pin "P$47") (pinfunction "CAP2_P$47") (pintype "bidirectional"))
    )
    (net (code "37") (name "Net-(U$3-SENSOR_CAPN(GPIO38{slash}ADC1_CH2{slash}RTC_GPIO2))") (class "Default")
      (node (ref "C4-ESP") (pin "1") (pinfunction "1_1") (pintype "passive"))
      (node (ref "U$3") (pin "P$7") (pinfunction "SENSOR_CAPN(GPIO38/ADC1_CH2/RTC_GPIO2)_P$7") (pintype "bidirectional"))
    )
    (net (code "38") (name "Net-(U$3-SENSOR_CAPP(GPIO37{slash}ADC1_CH1{slash}RTC_GPIO1))") (class "Default")
      (node (ref "C3-ESP") (pin "1") (pinfunction "1_1") (pintype "passive"))
      (node (ref "U$3") (pin "P$6") (pinfunction "SENSOR_CAPP(GPIO37/ADC1_CH1/RTC_GPIO1)_P$6") (pintype "bidirectional"))
    )
    (net (code "39") (name "Net-(U$3-SENSOR_VN(GPIO39{slash}ADC1_CH3{slash}RTC_GPIO3))") (class "Default")
      (node (ref "C4-ESP") (pin "2") (pinfunction "2_2") (pintype "passive"))
      (node (ref "U$3") (pin "P$8") (pinfunction "SENSOR_VN(GPIO39/ADC1_CH3/RTC_GPIO3)_P$8") (pintype "bidirectional"))
    )
    (net (code "40") (name "Net-(U$3-SENSOR_VP(GPIO36{slash}ADC1_CH0{slash}RTC_GPIO0))") (class "Default")
      (node (ref "C3-ESP") (pin "2") (pinfunction "2_2") (pintype "passive"))
      (node (ref "U$3") (pin "P$5") (pinfunction "SENSOR_VP(GPIO36/ADC1_CH0/RTC_GPIO0)_P$5") (pintype "bidirectional"))
    )
    (net (code "41") (name "Net-(U.FL-SIGNAL)") (class "Default")
      (node (ref "JP3") (pin "2") (pinfunction "2_2") (pintype "passive"))
      (node (ref "U.FL") (pin "3") (pinfunction "SIGNAL_3") (pintype "passive"))
    )
    (net (code "42") (name "Net-(U2-FB)") (class "Default")
      (node (ref "R1_PWRFB") (pin "1") (pinfunction "1_1") (pintype "passive"))
      (node (ref "R2_PWRFB") (pin "2") (pinfunction "2_2") (pintype "passive"))
      (node (ref "U2") (pin "10") (pinfunction "FB_10") (pintype "passive"))
    )
    (net (code "43") (name "Net-(U2-L)") (class "Default")
      (node (ref "U$5") (pin "P$2") (pinfunction "P$2_P$2") (pintype "bidirectional"))
      (node (ref "U2") (pin "3") (pinfunction "L_3") (pintype "passive"))
    )
    (net (code "44") (name "Net-(U2-UVLO)") (class "Default")
      (node (ref "R1_PWRUVLO") (pin "1") (pinfunction "1_1") (pintype "passive"))
      (node (ref "R2_PWRUVLO") (pin "2") (pinfunction "2_2") (pintype "passive"))
      (node (ref "U2") (pin "7") (pinfunction "UVLO_7") (pintype "passive"))
    )
    (net (code "45") (name "Net-(U2-VAUX)") (class "Default")
      (node (ref "C3_PWR") (pin "2") (pinfunction "2_2") (pintype "passive"))
      (node (ref "U2") (pin "1") (pinfunction "VAUX_1") (pintype "passive"))
    )
    (net (code "46") (name "Net-(U3-PROG)") (class "Default")
      (node (ref "R2_BAT") (pin "2") (pinfunction "2_2") (pintype "passive"))
      (node (ref "U3") (pin "5") (pinfunction "PROG_5") (pintype "input"))
    )
    (net (code "47") (name "Net-(U3-STAT)") (class "Default")
      (node (ref "R1_BAT") (pin "1") (pinfunction "1_1") (pintype "passive"))
      (node (ref "U3") (pin "1") (pinfunction "STAT_1") (pintype "output"))
    )
    (net (code "48") (name "Net-(U4-3V3OUT)") (class "Default")
      (node (ref "C6_USB") (pin "1") (pinfunction "1_1") (pintype "passive"))
      (node (ref "U4") (pin "13") (pinfunction "3V3OUT_13") (pintype "bidirectional"))
      (node (ref "U4") (pin "14") (pinfunction "~{RESET}_14") (pintype "bidirectional"))
      (node (ref "U4") (pin "3") (pinfunction "VCCIO_3") (pintype "bidirectional"))
    )
    (net (code "49") (name "Net-(U4-CBUS1)") (class "Default")
      (node (ref "LED_TX") (pin "C") (pinfunction "C_C") (pintype "passive"))
      (node (ref "U4") (pin "17") (pinfunction "CBUS1_17") (pintype "bidirectional"))
    )
    (net (code "50") (name "Net-(U4-CBUS2)") (class "Default")
      (node (ref "LED_RX") (pin "C") (pinfunction "C_C") (pintype "passive"))
      (node (ref "U4") (pin "10") (pinfunction "CBUS2_10") (pintype "bidirectional"))
    )
    (net (code "51") (name "Net-(U4-USBDM)") (class "Default")
      (node (ref "R6_USB") (pin "2") (pinfunction "2_2") (pintype "passive"))
      (node (ref "U4") (pin "12") (pinfunction "USBDM_12") (pintype "bidirectional"))
    )
    (net (code "52") (name "Net-(U4-USBDP)") (class "Default")
      (node (ref "R5_USB") (pin "2") (pinfunction "2_2") (pintype "passive"))
      (node (ref "U4") (pin "11") (pinfunction "USBDP_11") (pintype "bidirectional"))
    )
    (net (code "53") (name "Net-(U4-~{DTR})") (class "Default")
      (node (ref "U4") (pin "1") (pinfunction "~{DTR}_1") (pintype "bidirectional"))
      (node (ref "UMH3NFHATN") (pin "2") (pinfunction "2_2") (pintype "bidirectional"))
      (node (ref "UMH3NFHATN") (pin "4") (pinfunction "4_4") (pintype "bidirectional"))
    )
    (net (code "54") (name "Net-(U4-~{RTS})") (class "Default")
      (node (ref "U4") (pin "2") (pinfunction "~{RTS}_2") (pintype "bidirectional"))
      (node (ref "UMH3NFHATN") (pin "1") (pinfunction "1_1") (pintype "bidirectional"))
      (node (ref "UMH3NFHATN") (pin "5") (pinfunction "5_5") (pintype "bidirectional"))
    )
    (net (code "55") (name "RESET") (class "Default")
      (node (ref "C1_SUP") (pin "2") (pinfunction "2_2") (pintype "passive"))
      (node (ref "R1-ESP") (pin "1") (pinfunction "1_1") (pintype "passive"))
      (node (ref "RESET_BUTTON") (pin "3") (pinfunction "3_3") (pintype "passive"))
      (node (ref "RESET_BUTTON") (pin "4") (pinfunction "4_4") (pintype "passive"))
      (node (ref "U$2") (pin "P$1") (pinfunction "VOUT_P$1") (pintype "bidirectional"))
      (node (ref "U$3") (pin "P$9") (pinfunction "CHIP_PU_P$9") (pintype "bidirectional"))
      (node (ref "UMH3NFHATN") (pin "6") (pinfunction "6_6") (pintype "bidirectional"))
    )
    (net (code "56") (name "RGB_B") (class "Default")
      (node (ref "R_B") (pin "1") (pinfunction "1_1") (pintype "passive"))
      (node (ref "U$3") (pin "P$14") (pinfunction "(ADC2_CH8/RTC_GPIO6/DAC_1)GPIO25_P$14") (pintype "bidirectional"))
    )
    (net (code "57") (name "RGB_G") (class "Default")
      (node (ref "R_G") (pin "1") (pinfunction "1_1") (pintype "passive"))
      (node (ref "U$3") (pin "P$15") (pinfunction "(ADC2_CH9/RTC_GPIO7/DAC_2)GPIO26_P$15") (pintype "bidirectional"))
    )
    (net (code "58") (name "RGB_R") (class "Default")
      (node (ref "R_R") (pin "1") (pinfunction "1_1") (pintype "passive"))
      (node (ref "U$3") (pin "P$16") (pinfunction "(ADC2_CH7/RTC_GPIO17/TOUCH7)GPIO27_P$16") (pintype "bidirectional"))
    )
    (net (code "59") (name "RX0") (class "Default")
      (node (ref "U$3") (pin "P$40") (pinfunction "(GPIO3/CLK_OUT2)U0RXD_P$40") (pintype "bidirectional"))
      (node (ref "U4") (pin "20") (pinfunction "TXD_20") (pintype "bidirectional"))
    )
    (net (code "60") (name "SCK") (class "Default")
      (node (ref "J2") (pin "4") (pinfunction "4_4") (pintype "passive"))
      (node (ref "U$3") (pin "P$35") (pinfunction "(HS1_DATA7)GPIO18_P$35") (pintype "bidirectional"))
    )
    (net (code "61") (name "SCL") (class "Default")
      (node (ref "J1") (pin "4") (pinfunction "4_4") (pintype "passive"))
      (node (ref "R2_PINH") (pin "1") (pinfunction "1_1") (pintype "passive"))
      (node (ref "SENSOR1") (pin "5") (pinfunction "SCL_5") (pintype "input"))
      (node (ref "SENSOR2") (pin "4") (pinfunction "SCK_4") (pintype "input"))
      (node (ref "U$3") (pin "P$39") (pinfunction "(U0RTS)GPIO22_P$39") (pintype "bidirectional"))
    )
    (net (code "62") (name "SDA") (class "Default")
      (node (ref "J1") (pin "3") (pinfunction "3_3") (pintype "passive"))
      (node (ref "R1_PINH") (pin "1") (pinfunction "1_1") (pintype "passive"))
      (node (ref "SENSOR1") (pin "2") (pinfunction "SDA_2") (pintype "bidirectional"))
      (node (ref "SENSOR2") (pin "3") (pinfunction "SDI_3") (pintype "bidirectional"))
      (node (ref "U$3") (pin "P$42") (pinfunction "GPIO21_P$42") (pintype "bidirectional"))
    )
    (net (code "63") (name "TX0") (class "Default")
      (node (ref "R5-ESP") (pin "2") (pinfunction "2_2") (pintype "passive"))
      (node (ref "U4") (pin "4") (pinfunction "RXD_4") (pintype "bidirectional"))
    )
    (net (code "64") (name "USB_DATA_N") (class "Default")
      (node (ref "C1_USB") (pin "1") (pinfunction "1_1") (pintype "passive"))
      (node (ref "MOLEX") (pin "2") (pinfunction "D-_2") (pintype "bidirectional"))
      (node (ref "R6_USB") (pin "1") (pinfunction "1_1") (pintype "passive"))
    )
    (net (code "65") (name "USB_DATA_P") (class "Default")
      (node (ref "C2_USB") (pin "1") (pinfunction "1_1") (pintype "passive"))
      (node (ref "MOLEX") (pin "3") (pinfunction "D+_3") (pintype "bidirectional"))
      (node (ref "R5_USB") (pin "1") (pinfunction "1_1") (pintype "passive"))
    )
    (net (code "66") (name "VDD3P3_SDIO") (class "Default")
      (node (ref "J2") (pin "13") (pinfunction "13_13") (pintype "passive"))
      (node (ref "U$3") (pin "P$26") (pinfunction "VDD_SDIO_P$26") (pintype "bidirectional"))
    )
    (net (code "67") (name "VIN_BAT") (class "Default")
      (node (ref "C2_BAT") (pin "2") (pinfunction "2_2") (pintype "passive"))
      (node (ref "J1") (pin "13") (pinfunction "13_13") (pintype "passive"))
      (node (ref "Q1") (pin "3") (pinfunction "D_3") (pintype "bidirectional"))
      (node (ref "R6-ESP") (pin "2") (pinfunction "2_2") (pintype "passive"))
      (node (ref "U$4") (pin "P$2") (pinfunction "P_P$2") (pintype "bidirectional"))
      (node (ref "U$4") (pin "P$5") (pinfunction "P_P$5") (pintype "bidirectional"))
      (node (ref "U$4") (pin "P$6") (pinfunction "P_P$6") (pintype "bidirectional"))
      (node (ref "U3") (pin "3") (pinfunction "VBAT_3") (pintype "power_in"))
    )
    (net (code "68") (name "VIN_USB") (class "Default")
      (node (ref "C1_BAT") (pin "2") (pinfunction "2_2") (pintype "passive"))
      (node (ref "C4_USB") (pin "1") (pinfunction "1_1") (pintype "passive"))
      (node (ref "C5_USB") (pin "1") (pinfunction "1_1") (pintype "passive"))
      (node (ref "D3") (pin "2") (pinfunction "ANODE_2") (pintype "bidirectional"))
      (node (ref "J1") (pin "14") (pinfunction "14_14") (pintype "passive"))
      (node (ref "LED_BAT") (pin "A") (pinfunction "A_A") (pintype "passive"))
      (node (ref "PFMF.050.2") (pin "1") (pinfunction "1_1") (pintype "passive"))
      (node (ref "Q1") (pin "1") (pinfunction "G_1") (pintype "bidirectional"))
      (node (ref "R1_PWRUSB") (pin "2") (pinfunction "2_2") (pintype "passive"))
      (node (ref "U3") (pin "4") (pinfunction "VIN_4") (pintype "power_in"))
      (node (ref "U4") (pin "15") (pinfunction "VCC_15") (pintype "bidirectional"))
    )
    (net (code "69") (name "VUSB") (class "Default")
      (node (ref "C3_USB") (pin "1") (pinfunction "1_1") (pintype "passive"))
      (node (ref "MOLEX") (pin "1") (pinfunction "VBUS_1") (pintype "power_in"))
      (node (ref "PFMF.050.2") (pin "2") (pinfunction "2_2") (pintype "passive"))
    )
    (net (code "70") (name "XTAL_N") (class "Default")
      (node (ref "C2-Q1") (pin "2") (pinfunction "2_2") (pintype "passive"))
      (node (ref "Q40M") (pin "3") (pinfunction "OUT/IN_3") (pintype "bidirectional"))
      (node (ref "U$3") (pin "P$44") (pinfunction "XTAL_N_P$44") (pintype "bidirectional"))
    )
    (net (code "71") (name "XTAL_P") (class "Default")
      (node (ref "C1-Q1") (pin "2") (pinfunction "2_2") (pintype "passive"))
      (node (ref "Q40M") (pin "1") (pinfunction "IN/OUT_1") (pintype "bidirectional"))
      (node (ref "U$3") (pin "P$45") (pinfunction "XTAL_P_P$45") (pintype "bidirectional"))
    )
    (net (code "72") (name "unconnected-(MOLEX-ID-Pad4)") (class "Default")
      (node (ref "MOLEX") (pin "4") (pinfunction "ID_4") (pintype "passive"))
    )
    (net (code "73") (name "unconnected-(U$2-N.C.4-PadP$4)") (class "Default")
      (node (ref "U$2") (pin "P$4") (pinfunction "N.C.4_P$4") (pintype "bidirectional"))
    )
    (net (code "74") (name "unconnected-(U$2-N.C.5-PadP$5)") (class "Default")
      (node (ref "U$2") (pin "P$5") (pinfunction "N.C.5_P$5") (pintype "bidirectional"))
    )
    (net (code "75") (name "unconnected-(U4-CBUS0-Pad18)") (class "Default")
      (node (ref "U4") (pin "18") (pinfunction "CBUS0_18") (pintype "bidirectional"))
    )
    (net (code "76") (name "unconnected-(U4-CBUS3-Pad19)") (class "Default")
      (node (ref "U4") (pin "19") (pinfunction "CBUS3_19") (pintype "bidirectional"))
    )
    (net (code "77") (name "unconnected-(U4-~{CTS}-Pad9)") (class "Default")
      (node (ref "U4") (pin "9") (pinfunction "~{CTS}_9") (pintype "bidirectional"))
    )
    (net (code "78") (name "unconnected-(U4-~{DCD}-Pad8)") (class "Default")
      (node (ref "U4") (pin "8") (pinfunction "~{DCD}_8") (pintype "bidirectional"))
    )
    (net (code "79") (name "unconnected-(U4-~{DSR}-Pad7)") (class "Default")
      (node (ref "U4") (pin "7") (pinfunction "~{DSR}_7") (pintype "bidirectional"))
    )
    (net (code "80") (name "unconnected-(U4-~{RI}-Pad5)") (class "Default")
      (node (ref "U4") (pin "5") (pinfunction "~{RI}_5") (pintype "bidirectional"))
    )
  )
)
